# raspberry_aux_board_connectors.net
KiCad netlist of a schematic drawn in EAGLE
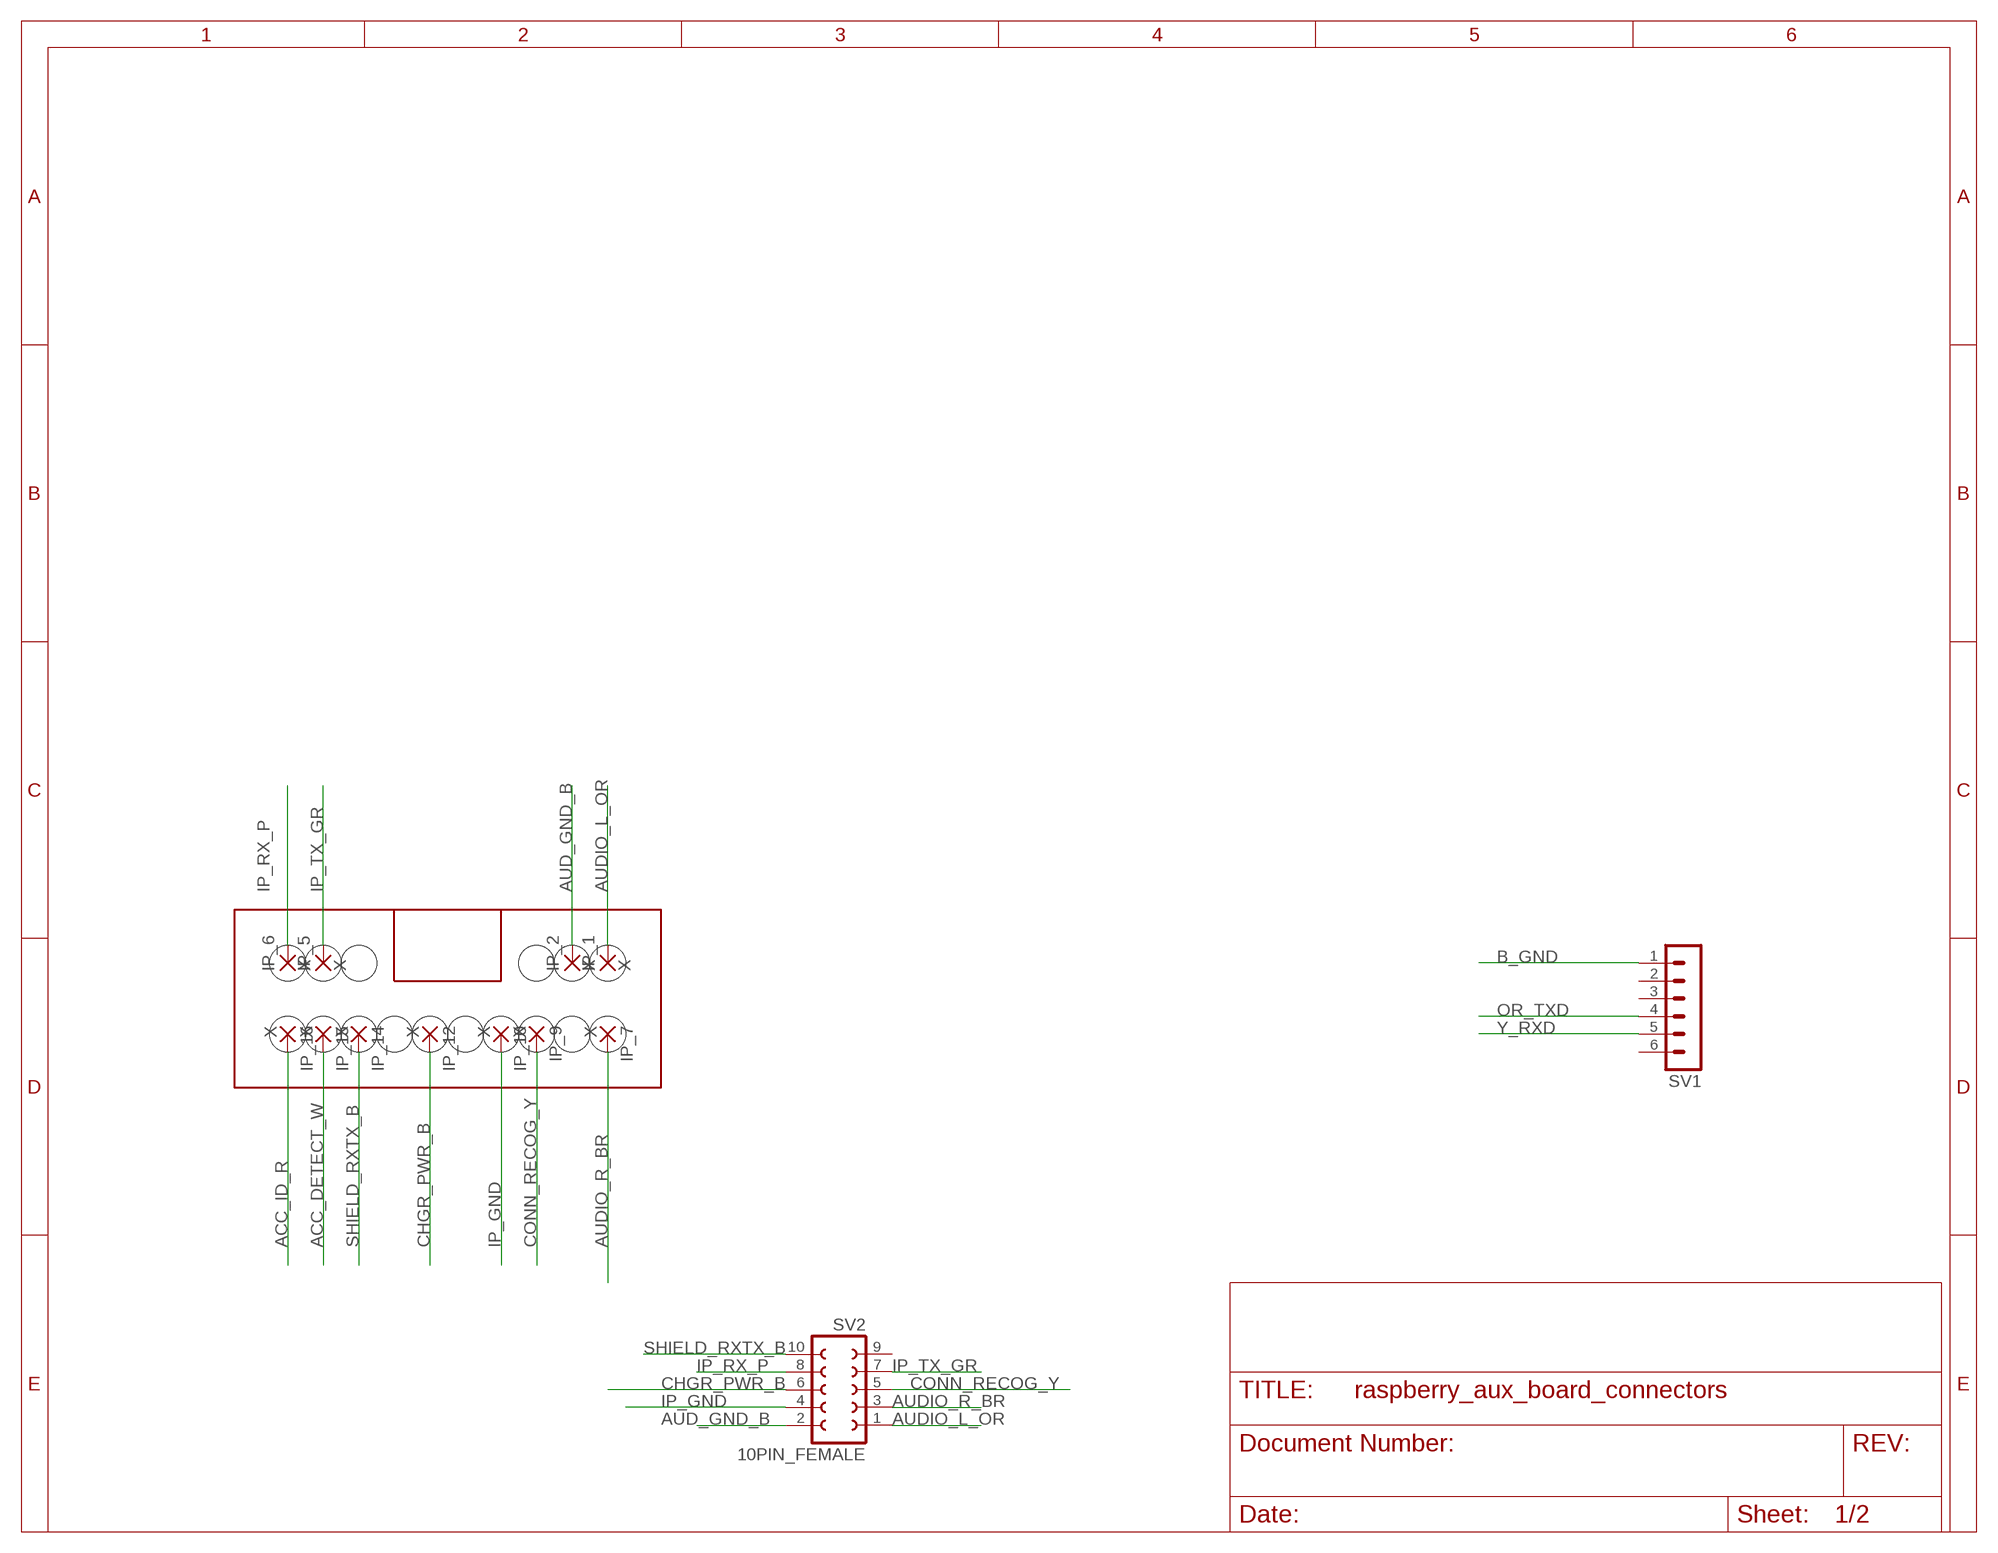
[diagram p0: schematic, sheet 1]

(export (version "E")
  (design (tool "Eeschema 10.0.6"))
  (components
    (comp (ref "IP_1")
      (value "X")
      (footprint "eagle-import:2,15_1,0")
      (libsource (lib "eagle-import") (part "2,15/1,0"))
    )
    (comp (ref "IP_2")
      (value "X")
      (footprint "eagle-import:2,15_1,0")
      (libsource (lib "eagle-import") (part "2,15/1,0"))
    )
    (comp (ref "IP_5")
      (value "X")
      (footprint "eagle-import:2,15_1,0")
      (libsource (lib "eagle-import") (part "2,15/1,0"))
    )
    (comp (ref "IP_6")
      (value "X")
      (footprint "eagle-import:2,15_1,0")
      (libsource (lib "eagle-import") (part "2,15/1,0"))
    )
    (comp (ref "IP_7")
      (value "X")
      (footprint "eagle-import:2,15_1,0")
      (libsource (lib "eagle-import") (part "2,15/1,0"))
    )
    (comp (ref "IP_9")
      (value "X")
      (footprint "eagle-import:2,15_1,0")
      (libsource (lib "eagle-import") (part "2,15/1,0"))
    )
    (comp (ref "IP_10")
      (value "X")
      (footprint "eagle-import:2,15_1,0")
      (libsource (lib "eagle-import") (part "2,15/1,0"))
    )
    (comp (ref "IP_12")
      (value "X")
      (footprint "eagle-import:2,15_1,0")
      (libsource (lib "eagle-import") (part "2,15/1,0"))
    )
    (comp (ref "IP_14")
      (value "X")
      (footprint "eagle-import:2,15_1,0")
      (libsource (lib "eagle-import") (part "2,15/1,0"))
    )
    (comp (ref "IP_15")
      (value "X")
      (footprint "eagle-import:2,15_1,0")
      (libsource (lib "eagle-import") (part "2,15/1,0"))
    )
    (comp (ref "IP_16")
      (value "X")
      (footprint "eagle-import:2,15_1,0")
      (libsource (lib "eagle-import") (part "2,15/1,0"))
    )
    (comp (ref "SV1")
      (value "MA06-1")
      (footprint "eagle-import:MA06-1")
      (libsource (lib "eagle-import") (part "MA06-1"))
    )
    (comp (ref "SV2")
      (value "10PIN_FEMALE")
      (footprint "eagle-import:FE05-2")
      (libsource (lib "eagle-import") (part "FE05-2"))
    )
  )
  (nets
    (net (code "1") (name "ACC_DETECT_W") (class "Default")
      (node (ref "IP_15") (pin "1") (pinfunction "P_1") (pintype "passive"))
    )
    (net (code "2") (name "ACC_ID_R") (class "Default")
      (node (ref "IP_16") (pin "1") (pinfunction "P_1") (pintype "passive"))
    )
    (net (code "3") (name "AUDIO_L_OR") (class "Default")
      (node (ref "IP_1") (pin "1") (pinfunction "P_1") (pintype "passive"))
      (node (ref "SV2") (pin "1") (pinfunction "1_1") (pintype "passive"))
    )
    (net (code "4") (name "AUDIO_R_BR") (class "Default")
      (node (ref "IP_7") (pin "1") (pinfunction "P_1") (pintype "passive"))
      (node (ref "SV2") (pin "3") (pinfunction "3_3") (pintype "passive"))
    )
    (net (code "5") (name "AUD_GND_B") (class "Default")
      (node (ref "IP_2") (pin "1") (pinfunction "P_1") (pintype "passive"))
      (node (ref "SV2") (pin "2") (pinfunction "2_2") (pintype "passive"))
    )
    (net (code "6") (name "B_GND") (class "Default")
      (node (ref "SV1") (pin "1") (pinfunction "1_1") (pintype "passive"))
    )
    (net (code "7") (name "CHGR_PWR_B") (class "Default")
      (node (ref "IP_12") (pin "1") (pinfunction "P_1") (pintype "passive"))
      (node (ref "SV2") (pin "6") (pinfunction "6_6") (pintype "passive"))
    )
    (net (code "8") (name "CONN_RECOG_Y") (class "Default")
      (node (ref "IP_9") (pin "1") (pinfunction "P_1") (pintype "passive"))
      (node (ref "SV2") (pin "5") (pinfunction "5_5") (pintype "passive"))
    )
    (net (code "9") (name "IP_GND") (class "Default")
      (node (ref "IP_10") (pin "1") (pinfunction "P_1") (pintype "passive"))
      (node (ref "SV2") (pin "4") (pinfunction "4_4") (pintype "passive"))
    )
    (net (code "10") (name "IP_RX_P") (class "Default")
      (node (ref "IP_6") (pin "1") (pinfunction "P_1") (pintype "passive"))
      (node (ref "SV2") (pin "8") (pinfunction "8_8") (pintype "passive"))
    )
    (net (code "11") (name "IP_TX_GR") (class "Default")
      (node (ref "IP_5") (pin "1") (pinfunction "P_1") (pintype "passive"))
      (node (ref "SV2") (pin "7") (pinfunction "7_7") (pintype "passive"))
    )
    (net (code "12") (name "OR_TXD") (class "Default")
      (node (ref "SV1") (pin "4") (pinfunction "4_4") (pintype "passive"))
    )
    (net (code "13") (name "SHIELD_RXTX_B") (class "Default")
      (node (ref "IP_14") (pin "1") (pinfunction "P_1") (pintype "passive"))
      (node (ref "SV2") (pin "10") (pinfunction "10_10") (pintype "passive"))
    )
    (net (code "14") (name "Y_RXD") (class "Default")
      (node (ref "SV1") (pin "5") (pinfunction "5_5") (pintype "passive"))
    )
    (net (code "15") (name "unconnected-(SV1-Pad2)") (class "Default")
      (node (ref "SV1") (pin "2") (pinfunction "2_2") (pintype "passive"))
    )
    (net (code "16") (name "unconnected-(SV1-Pad3)") (class "Default")
      (node (ref "SV1") (pin "3") (pinfunction "3_3") (pintype "passive"))
    )
    (net (code "17") (name "unconnected-(SV1-Pad6)") (class "Default")
      (node (ref "SV1") (pin "6") (pinfunction "6_6") (pintype "passive"))
    )
    (net (code "18") (name "unconnected-(SV2-Pad9)") (class "Default")
      (node (ref "SV2") (pin "9") (pinfunction "9_9") (pintype "passive"))
    )
  )
)
